# PAM8403_Amplifier_Board_R2.net
KiCad netlist of a schematic drawn in EAGLE
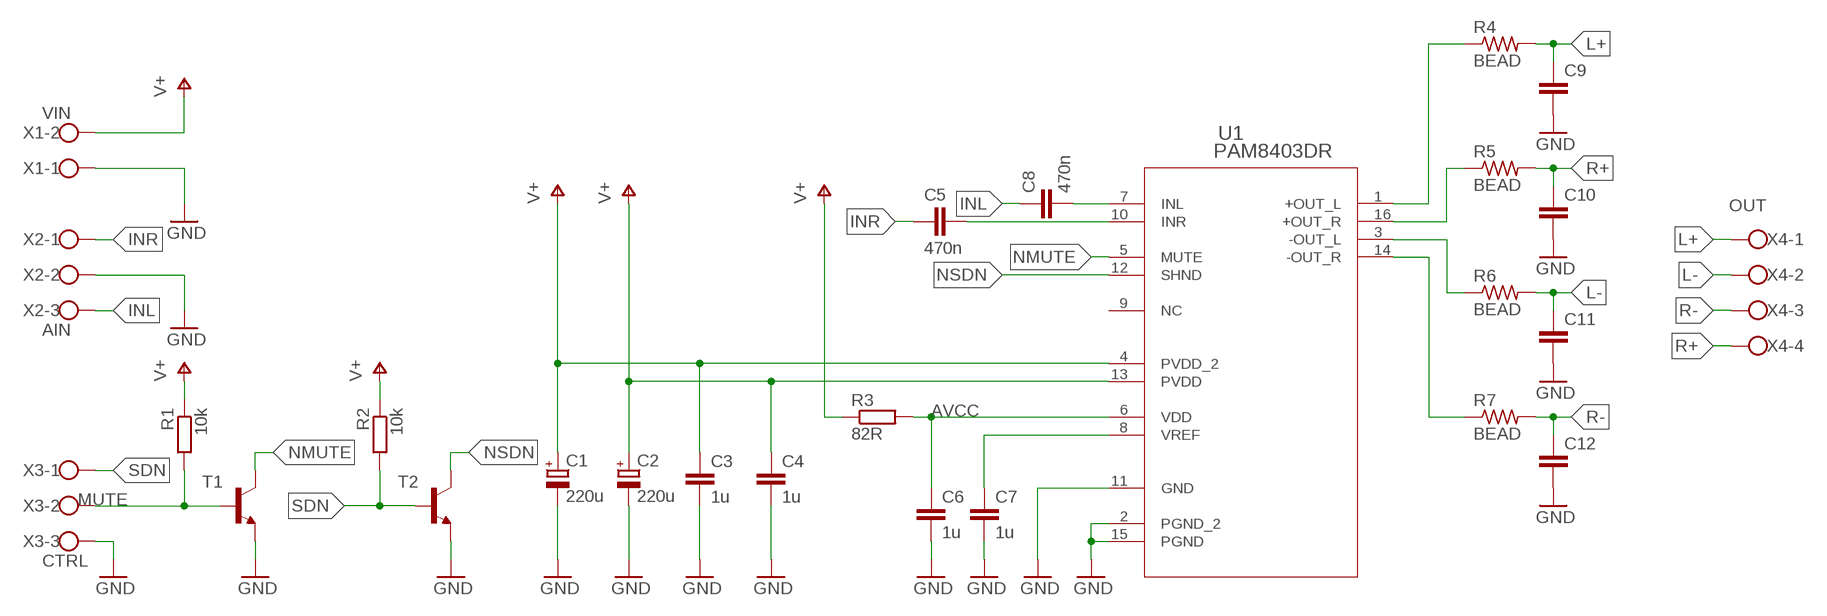
[diagram p0: schematic, sheet 1]

(export (version "E")
  (design (tool "Eeschema 10.0.6"))
  (components
    (comp (ref "C1")
      (value "220u")
      (footprint "eagle-import:UD-10X10_NICHICON")
      (libsource (lib "eagle-import") (part "CPOL-EUUD-10X10"))
    )
    (comp (ref "C2")
      (value "220u")
      (footprint "eagle-import:UD-10X10_NICHICON")
      (libsource (lib "eagle-import") (part "CPOL-EUUD-10X10"))
    )
    (comp (ref "C3")
      (value "1u")
      (footprint "eagle-import:C0805")
      (libsource (lib "eagle-import") (part "C-EUC0805"))
    )
    (comp (ref "C4")
      (value "1u")
      (footprint "eagle-import:C0805")
      (libsource (lib "eagle-import") (part "C-EUC0805"))
    )
    (comp (ref "C5")
      (value "470n")
      (footprint "eagle-import:C1206")
      (libsource (lib "eagle-import") (part "C-EUC1206"))
    )
    (comp (ref "C6")
      (value "1u")
      (footprint "eagle-import:C0805")
      (libsource (lib "eagle-import") (part "C-EUC0805"))
    )
    (comp (ref "C7")
      (value "1u")
      (footprint "eagle-import:C0805")
      (libsource (lib "eagle-import") (part "C-EUC0805"))
    )
    (comp (ref "C8")
      (value "470n")
      (footprint "eagle-import:C1206")
      (libsource (lib "eagle-import") (part "C-EUC1206"))
    )
    (comp (ref "C9")
      (value "C-EUC0603")
      (footprint "eagle-import:C0603")
      (libsource (lib "eagle-import") (part "C-EUC0603"))
    )
    (comp (ref "C10")
      (value "C-EUC0603")
      (footprint "eagle-import:C0603")
      (libsource (lib "eagle-import") (part "C-EUC0603"))
    )
    (comp (ref "C11")
      (value "C-EUC0603")
      (footprint "eagle-import:C0603")
      (libsource (lib "eagle-import") (part "C-EUC0603"))
    )
    (comp (ref "C12")
      (value "C-EUC0603")
      (footprint "eagle-import:C0603")
      (libsource (lib "eagle-import") (part "C-EUC0603"))
    )
    (comp (ref "R1")
      (value "10k")
      (footprint "eagle-import:R0603")
      (libsource (lib "eagle-import") (part "R-EU_R0603"))
    )
    (comp (ref "R2")
      (value "10k")
      (footprint "eagle-import:R0603")
      (libsource (lib "eagle-import") (part "R-EU_R0603"))
    )
    (comp (ref "R3")
      (value "82R")
      (footprint "eagle-import:R1206")
      (libsource (lib "eagle-import") (part "R-EU_R1206"))
    )
    (comp (ref "R4")
      (value "BEAD")
      (footprint "eagle-import:R0805")
      (libsource (lib "eagle-import") (part "R-US_R0805"))
    )
    (comp (ref "R5")
      (value "BEAD")
      (footprint "eagle-import:R0805")
      (libsource (lib "eagle-import") (part "R-US_R0805"))
    )
    (comp (ref "R6")
      (value "BEAD")
      (footprint "eagle-import:R0805")
      (libsource (lib "eagle-import") (part "R-US_R0805"))
    )
    (comp (ref "R7")
      (value "BEAD")
      (footprint "eagle-import:R0805")
      (libsource (lib "eagle-import") (part "R-US_R0805"))
    )
    (comp (ref "T1")
      (value "MMBT3904LT1-NPN-SOT23-BEC")
      (footprint "eagle-import:SOT23-BEC")
      (libsource (lib "eagle-import") (part "-NPN-SOT23-BECMMBT3904LT1"))
    )
    (comp (ref "T2")
      (value "MMBT3904LT1-NPN-SOT23-BEC")
      (footprint "eagle-import:SOT23-BEC")
      (libsource (lib "eagle-import") (part "-NPN-SOT23-BECMMBT3904LT1"))
    )
    (comp (ref "U1")
      (value "PAM8403DR")
      (footprint "eagle-import:SOIC_8403DR_DIO")
      (fields (field (name "COPYRIGHT") "Copyright (C) 2023 Ultra Librarian. All rights reserved."))
      (libsource (lib "eagle-import") (part "PAM8403DR"))
    )
    (comp (ref "X1")
      (value "VIN")
      (footprint "eagle-import:W237-102")
      (fields (field (name "MPN") "237-102"))
      (libsource (lib "eagle-import") (part "W237-102"))
    )
    (comp (ref "X2")
      (value "AIN")
      (footprint "eagle-import:W237-103")
      (fields (field (name "MPN") "237-103"))
      (libsource (lib "eagle-import") (part "W237-103"))
    )
    (comp (ref "X3")
      (value "CTRL")
      (footprint "eagle-import:W237-103")
      (fields (field (name "MPN") "237-103"))
      (libsource (lib "eagle-import") (part "W237-103"))
    )
    (comp (ref "X4")
      (value "OUT")
      (footprint "eagle-import:W237-4")
      (libsource (lib "eagle-import") (part "W237-4"))
    )
  )
  (nets
    (net (code "1") (name "/AVCC") (class "Default")
      (node (ref "C6") (pin "1") (pinfunction "1_1") (pintype "passive"))
      (node (ref "R3") (pin "2") (pinfunction "2_2") (pintype "passive"))
      (node (ref "U1") (pin "6") (pinfunction "VDD_6") (pintype "power_in"))
    )
    (net (code "2") (name "/MUTE") (class "Default")
      (node (ref "R1") (pin "2") (pinfunction "2_2") (pintype "passive"))
      (node (ref "T1") (pin "B") (pinfunction "B_B") (pintype "passive"))
      (node (ref "X3") (pin "2") (pinfunction "KL_2") (pintype "passive"))
    )
    (net (code "3") (name "GND") (class "Default")
      (node (ref "C1") (pin "-") (pinfunction "-_-") (pintype "passive"))
      (node (ref "C10") (pin "2") (pinfunction "2_2") (pintype "passive"))
      (node (ref "C11") (pin "2") (pinfunction "2_2") (pintype "passive"))
      (node (ref "C12") (pin "2") (pinfunction "2_2") (pintype "passive"))
      (node (ref "C2") (pin "-") (pinfunction "-_-") (pintype "passive"))
      (node (ref "C3") (pin "2") (pinfunction "2_2") (pintype "passive"))
      (node (ref "C4") (pin "2") (pinfunction "2_2") (pintype "passive"))
      (node (ref "C6") (pin "2") (pinfunction "2_2") (pintype "passive"))
      (node (ref "C7") (pin "2") (pinfunction "2_2") (pintype "passive"))
      (node (ref "C9") (pin "2") (pinfunction "2_2") (pintype "passive"))
      (node (ref "T1") (pin "E") (pinfunction "E_E") (pintype "passive"))
      (node (ref "T2") (pin "E") (pinfunction "E_E") (pintype "passive"))
      (node (ref "U1") (pin "11") (pinfunction "GND_11") (pintype "passive"))
      (node (ref "U1") (pin "15") (pinfunction "PGND_15") (pintype "passive"))
      (node (ref "U1") (pin "2") (pinfunction "PGND_2_2") (pintype "passive"))
      (node (ref "X1") (pin "1") (pinfunction "KL_1") (pintype "passive"))
      (node (ref "X2") (pin "2") (pinfunction "KL_2") (pintype "passive"))
      (node (ref "X3") (pin "3") (pinfunction "KL_3") (pintype "passive"))
    )
    (net (code "4") (name "INL") (class "Default")
      (node (ref "C8") (pin "1") (pinfunction "1_1") (pintype "passive"))
      (node (ref "X2") (pin "3") (pinfunction "KL_3") (pintype "passive"))
    )
    (net (code "5") (name "INR") (class "Default")
      (node (ref "C5") (pin "1") (pinfunction "1_1") (pintype "passive"))
      (node (ref "X2") (pin "1") (pinfunction "KL_1") (pintype "passive"))
    )
    (net (code "6") (name "L+") (class "Default")
      (node (ref "C9") (pin "1") (pinfunction "1_1") (pintype "passive"))
      (node (ref "R4") (pin "2") (pinfunction "2_2") (pintype "passive"))
      (node (ref "X4") (pin "1") (pinfunction "KL_1") (pintype "passive"))
    )
    (net (code "7") (name "L-") (class "Default")
      (node (ref "C11") (pin "1") (pinfunction "1_1") (pintype "passive"))
      (node (ref "R6") (pin "2") (pinfunction "2_2") (pintype "passive"))
      (node (ref "X4") (pin "2") (pinfunction "KL_2") (pintype "passive"))
    )
    (net (code "8") (name "NMUTE") (class "Default")
      (node (ref "T1") (pin "C") (pinfunction "C_C") (pintype "passive"))
      (node (ref "U1") (pin "5") (pinfunction "MUTE_5") (pintype "passive"))
    )
    (net (code "9") (name "NSDN") (class "Default")
      (node (ref "T2") (pin "C") (pinfunction "C_C") (pintype "passive"))
      (node (ref "U1") (pin "12") (pinfunction "SHND_12") (pintype "passive"))
    )
    (net (code "10") (name "Net-(U1-+OUT_L)") (class "Default")
      (node (ref "R4") (pin "1") (pinfunction "1_1") (pintype "passive"))
      (node (ref "U1") (pin "1") (pinfunction "+OUT_L_1") (pintype "output"))
    )
    (net (code "11") (name "Net-(U1-+OUT_R)") (class "Default")
      (node (ref "R5") (pin "1") (pinfunction "1_1") (pintype "passive"))
      (node (ref "U1") (pin "16") (pinfunction "+OUT_R_16") (pintype "output"))
    )
    (net (code "12") (name "Net-(U1--OUT_L)") (class "Default")
      (node (ref "R6") (pin "1") (pinfunction "1_1") (pintype "passive"))
      (node (ref "U1") (pin "3") (pinfunction "-OUT_L_3") (pintype "output"))
    )
    (net (code "13") (name "Net-(U1--OUT_R)") (class "Default")
      (node (ref "R7") (pin "1") (pinfunction "1_1") (pintype "passive"))
      (node (ref "U1") (pin "14") (pinfunction "-OUT_R_14") (pintype "output"))
    )
    (net (code "14") (name "Net-(U1-INL)") (class "Default")
      (node (ref "C8") (pin "2") (pinfunction "2_2") (pintype "passive"))
      (node (ref "U1") (pin "7") (pinfunction "INL_7") (pintype "passive"))
    )
    (net (code "15") (name "Net-(U1-INR)") (class "Default")
      (node (ref "C5") (pin "2") (pinfunction "2_2") (pintype "passive"))
      (node (ref "U1") (pin "10") (pinfunction "INR_10") (pintype "passive"))
    )
    (net (code "16") (name "Net-(U1-VREF)") (class "Default")
      (node (ref "C7") (pin "1") (pinfunction "1_1") (pintype "passive"))
      (node (ref "U1") (pin "8") (pinfunction "VREF_8") (pintype "power_in"))
    )
    (net (code "17") (name "R+") (class "Default")
      (node (ref "C10") (pin "1") (pinfunction "1_1") (pintype "passive"))
      (node (ref "R5") (pin "2") (pinfunction "2_2") (pintype "passive"))
      (node (ref "X4") (pin "4") (pinfunction "KL_4") (pintype "passive"))
    )
    (net (code "18") (name "R-") (class "Default")
      (node (ref "C12") (pin "1") (pinfunction "1_1") (pintype "passive"))
      (node (ref "R7") (pin "2") (pinfunction "2_2") (pintype "passive"))
      (node (ref "X4") (pin "3") (pinfunction "KL_3") (pintype "passive"))
    )
    (net (code "19") (name "SDN") (class "Default")
      (node (ref "R2") (pin "2") (pinfunction "2_2") (pintype "passive"))
      (node (ref "T2") (pin "B") (pinfunction "B_B") (pintype "passive"))
      (node (ref "X3") (pin "1") (pinfunction "KL_1") (pintype "passive"))
    )
    (net (code "20") (name "V+") (class "Default")
      (node (ref "C1") (pin "+") (pinfunction "+_+") (pintype "passive"))
      (node (ref "C2") (pin "+") (pinfunction "+_+") (pintype "passive"))
      (node (ref "C3") (pin "1") (pinfunction "1_1") (pintype "passive"))
      (node (ref "C4") (pin "1") (pinfunction "1_1") (pintype "passive"))
      (node (ref "R1") (pin "1") (pinfunction "1_1") (pintype "passive"))
      (node (ref "R2") (pin "1") (pinfunction "1_1") (pintype "passive"))
      (node (ref "R3") (pin "1") (pinfunction "1_1") (pintype "passive"))
      (node (ref "U1") (pin "13") (pinfunction "PVDD_13") (pintype "power_in"))
      (node (ref "U1") (pin "4") (pinfunction "PVDD_2_4") (pintype "power_in"))
      (node (ref "X1") (pin "2") (pinfunction "KL_2") (pintype "passive"))
    )
    (net (code "21") (name "unconnected-(U1-NC-Pad9)") (class "Default")
      (node (ref "U1") (pin "9") (pinfunction "NC_9") (pintype "no_connect"))
    )
  )
)
